# MSU_and_periphery.net
KiCad netlist of a schematic drawn in Altium Designer
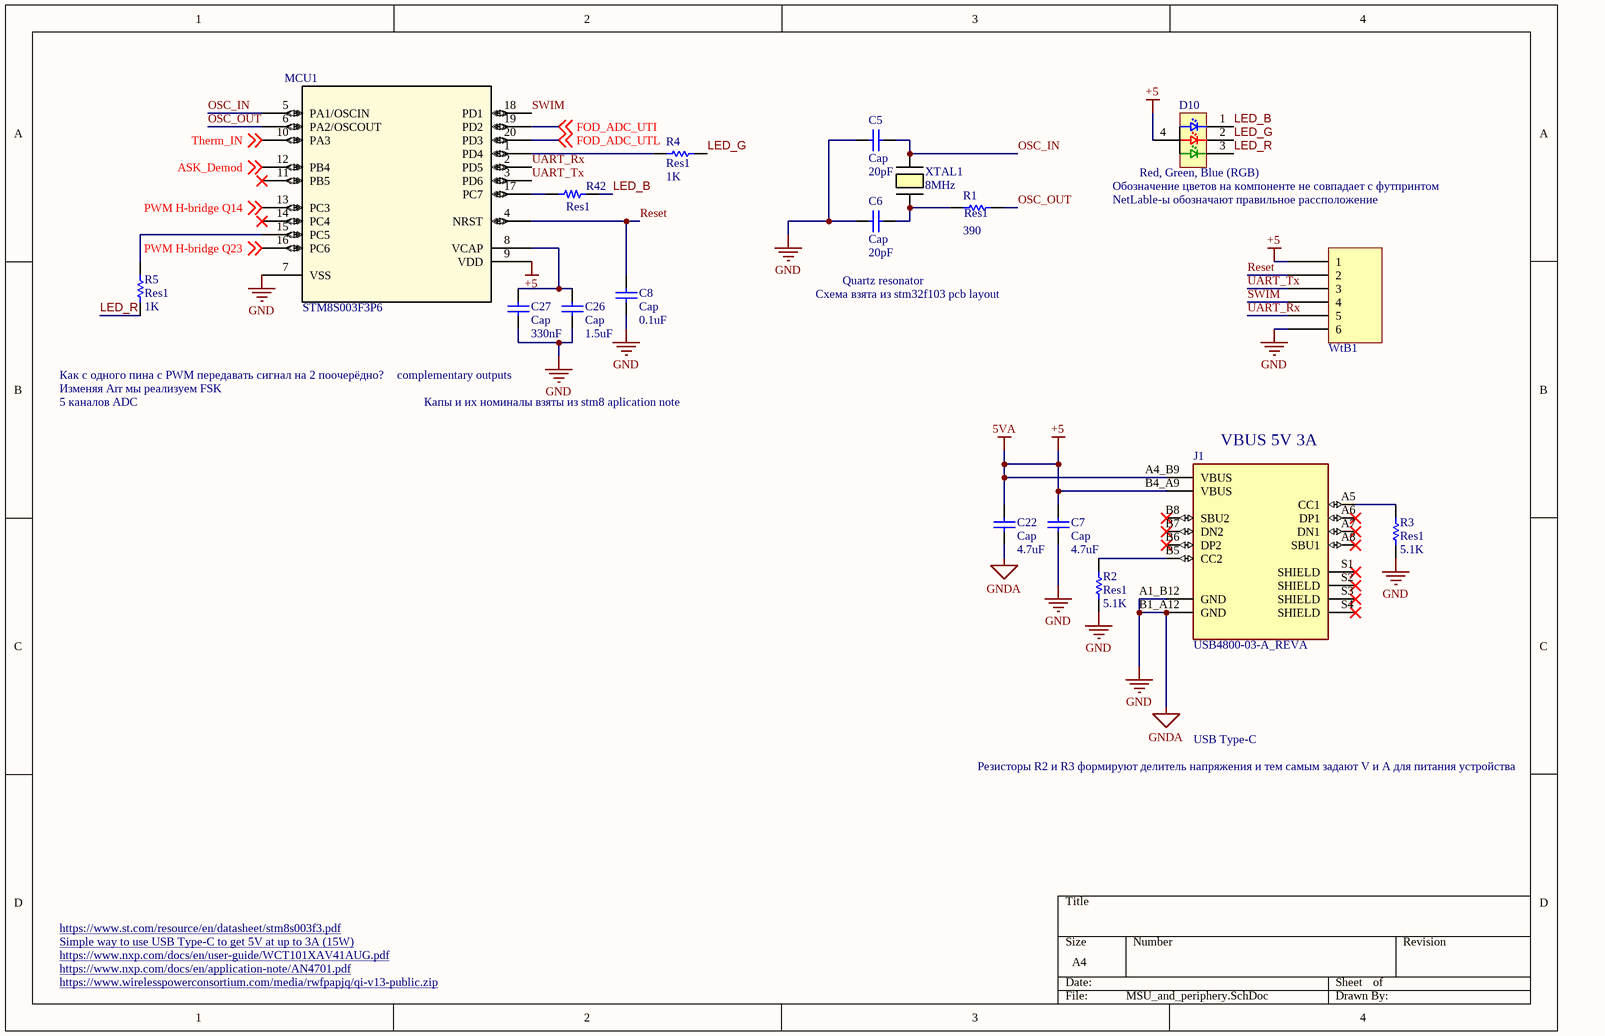
[diagram p0: MSU_and_periphery.SchDoc]

(export (version "E")
  (design (tool "Eeschema 10.0.6"))
  (components
    (comp (ref "C5")
      (value "Cap")
      (footprint "CAP 0402_1005")
      (description "Capacitor")
      (fields (field (name "ALTIUM_VALUE") "20pF") (field (name "PUBLISHER") "Altium Limited"))
      (libsource (lib "Miscellaneous Devices") (part "Cap"))
    )
    (comp (ref "C6")
      (value "Cap")
      (footprint "CAP 0402_1005")
      (description "Capacitor")
      (fields (field (name "ALTIUM_VALUE") "20pF") (field (name "PUBLISHER") "Altium Limited"))
      (libsource (lib "Miscellaneous Devices") (part "Cap"))
    )
    (comp (ref "C7")
      (value "Cap")
      (footprint "CAP 0402_1005")
      (description "Capacitor")
      (fields (field (name "ALTIUM_VALUE") "4.7uF") (field (name "PUBLISHER") "Altium Limited"))
      (libsource (lib "Miscellaneous Devices") (part "Cap"))
    )
    (comp (ref "C8")
      (value "Cap")
      (footprint "CAP 0402_1005")
      (description "Capacitor")
      (fields (field (name "ALTIUM_VALUE") "0.1uF") (field (name "PUBLISHER") "Altium Limited"))
      (libsource (lib "Miscellaneous Devices") (part "Cap"))
    )
    (comp (ref "C22")
      (value "Cap")
      (footprint "CAP 0402_1005")
      (description "Capacitor")
      (fields (field (name "ALTIUM_VALUE") "4.7uF") (field (name "PUBLISHER") "Altium Limited"))
      (libsource (lib "Miscellaneous Devices") (part "Cap"))
    )
    (comp (ref "C26")
      (value "Cap")
      (footprint "CAP 0603_1608")
      (description "Capacitor")
      (fields (field (name "ALTIUM_VALUE") "1.5uF") (field (name "PUBLISHER") "Altium Limited"))
      (libsource (lib "Miscellaneous Devices") (part "Cap"))
    )
    (comp (ref "C27")
      (value "Cap")
      (footprint "CAP 0603_1608")
      (description "Capacitor")
      (fields (field (name "ALTIUM_VALUE") "330nF") (field (name "PUBLISHER") "Altium Limited"))
      (libsource (lib "Miscellaneous Devices") (part "Cap"))
    )
    (comp (ref "D10")
      (value "Red, Green, Blue (RGB)")
      (footprint "Citizen CL-505S-X-SD-T")
      (description "LED TRI TOP FIRING 1.0 X 1.0")
      (fields (field (name "PART NUMBER") "CL-505S-X-SD-T") (field (name "MANUFACTURER") "Citizen"))
      (libsource (lib "LED - Indication") (part "CL-505S-X-SD-T"))
    )
    (comp (ref "J1")
      (value "USB4800-03-A_REVA")
      (footprint "GCT_USB4800-03-A_REVA")
      (fields (field (name "MP") "USB4800-03-A") (field (name "MF") "Global Connector Technology"))
      (libsource (lib "USB4800-03-A_REVA") (part "USB4800-03-A_REVA"))
    )
    (comp (ref "MCU1")
      (value "STM8S003F3P6")
      (footprint "TSSOP20")
      (description "No Description Available")
      (libsource (lib "STM8S003F3P6") (part "STM8S003F3P6"))
    )
    (comp (ref "R1")
      (value "Res1")
      (footprint "RES 0603_1608")
      (description "Resistor")
      (fields (field (name "ALTIUM_VALUE") "390") (field (name "PUBLISHER") "Altium Limited"))
      (libsource (lib "Miscellaneous Devices") (part "Res1"))
    )
    (comp (ref "R2")
      (value "Res1")
      (footprint "RES 0402_1005")
      (description "Resistor")
      (fields (field (name "ALTIUM_VALUE") "5.1K") (field (name "PUBLISHER") "Altium Limited"))
      (libsource (lib "Miscellaneous Devices") (part "Res1"))
    )
    (comp (ref "R3")
      (value "Res1")
      (footprint "RES 0402_1005")
      (description "Resistor")
      (fields (field (name "ALTIUM_VALUE") "5.1K") (field (name "PUBLISHER") "Altium Limited"))
      (libsource (lib "Miscellaneous Devices") (part "Res1"))
    )
    (comp (ref "R4")
      (value "Res1")
      (footprint "RES 0402_1005")
      (description "Resistor")
      (fields (field (name "ALTIUM_VALUE") "1K") (field (name "PUBLISHER") "Altium Limited"))
      (libsource (lib "Miscellaneous Devices") (part "Res1"))
    )
    (comp (ref "R5")
      (value "Res1")
      (footprint "RES 0402_1005")
      (description "Resistor")
      (fields (field (name "ALTIUM_VALUE") "1K") (field (name "PUBLISHER") "Altium Limited"))
      (libsource (lib "Miscellaneous Devices") (part "Res1"))
    )
    (comp (ref "R42")
      (value "Res1")
      (footprint "RES 0402_1005")
      (description "0402 JUMPER ON TAPE AND REEL")
      (fields (field (name "PART NUMBER") "5112") (field (name "MANUFACTURER") "Keystone Electronics"))
      (libsource (lib "Resistors - Surface Mount - 0402") (part "5112"))
    )
    (comp (ref "WtB1")
      (value "~")
      (footprint "6W_connector")
      (description "Wire to board connector 6pin")
      (libsource (lib "WtB_6_connector") (part "WtB_6_connector"))
    )
    (comp (ref "XTAL1")
      (value "8MHz")
      (footprint "NDK NX5032GA")
      (libsource (lib "ECS-80-18-5PX-TR") (part "ECS-80-18-5PX-TR"))
    )
  )
  (nets
    (net (code "1") (name "+5") (class "Default")
      (node (ref "C22") (pin "1") (pinfunction "1_1") (pintype "passive"))
      (node (ref "C7") (pin "1") (pinfunction "1_1") (pintype "passive"))
      (node (ref "D10") (pin "4") (pinfunction "A3_4") (pintype "passive"))
      (node (ref "J1") (pin "A4_B9") (pinfunction "VBUS_A4_B9") (pintype "power_in"))
      (node (ref "J1") (pin "B4_A9") (pinfunction "VBUS_B4_A9") (pintype "power_in"))
      (node (ref "MCU1") (pin "9") (pinfunction "VDD_9") (pintype "power_in"))
      (node (ref "WtB1") (pin "1") (pinfunction "1_1") (pintype "passive"))
    )
    (net (code "2") (name "/LED_B") (class "Default")
      (node (ref "D10") (pin "1") (pinfunction "C1_1") (pintype "passive"))
      (node (ref "R42") (pin "2") (pinfunction "2_2") (pintype "passive"))
    )
    (net (code "3") (name "/LED_G") (class "Default")
      (node (ref "D10") (pin "2") (pinfunction "C2_2") (pintype "passive"))
      (node (ref "R4") (pin "1") (pinfunction "1_1") (pintype "passive"))
    )
    (net (code "4") (name "/LED_R") (class "Default")
      (node (ref "D10") (pin "3") (pinfunction "C3_3") (pintype "passive"))
      (node (ref "R5") (pin "1") (pinfunction "1_1") (pintype "passive"))
    )
    (net (code "5") (name "/OSC_IN") (class "Default")
      (node (ref "C5") (pin "1") (pinfunction "1_1") (pintype "passive"))
      (node (ref "MCU1") (pin "5") (pinfunction "PA1/OSCIN_5") (pintype "bidirectional"))
      (node (ref "XTAL1") (pin "1") (pinfunction "4_1") (pintype "passive"))
    )
    (net (code "6") (name "/OSC_OUT") (class "Default")
      (node (ref "MCU1") (pin "6") (pinfunction "PA2/OSCOUT_6") (pintype "bidirectional"))
      (node (ref "R1") (pin "2") (pinfunction "2_2") (pintype "passive"))
    )
    (net (code "7") (name "/Reset") (class "Default")
      (node (ref "C8") (pin "2") (pinfunction "2_2") (pintype "passive"))
      (node (ref "MCU1") (pin "4") (pinfunction "NRST_4") (pintype "bidirectional"))
      (node (ref "WtB1") (pin "2") (pinfunction "2_2") (pintype "passive"))
    )
    (net (code "8") (name "/SWIM") (class "Default")
      (node (ref "MCU1") (pin "18") (pinfunction "PD1_18") (pintype "bidirectional"))
      (node (ref "WtB1") (pin "4") (pinfunction "4_4") (pintype "passive"))
    )
    (net (code "9") (name "/UART_Rx") (class "Default")
      (node (ref "MCU1") (pin "2") (pinfunction "PD5_2") (pintype "bidirectional"))
      (node (ref "WtB1") (pin "5") (pinfunction "5_5") (pintype "passive"))
    )
    (net (code "10") (name "/UART_Tx") (class "Default")
      (node (ref "MCU1") (pin "3") (pinfunction "PD6_3") (pintype "bidirectional"))
      (node (ref "WtB1") (pin "3") (pinfunction "3_3") (pintype "passive"))
    )
    (net (code "11") (name "ASK_Demod") (class "Default")
      (node (ref "MCU1") (pin "12") (pinfunction "PB4_12") (pintype "bidirectional"))
    )
    (net (code "12") (name "FOD_ADC_UTI") (class "Default")
      (node (ref "MCU1") (pin "19") (pinfunction "PD2_19") (pintype "bidirectional"))
    )
    (net (code "13") (name "FOD_ADC_UTL") (class "Default")
      (node (ref "MCU1") (pin "20") (pinfunction "PD3_20") (pintype "bidirectional"))
    )
    (net (code "14") (name "GND") (class "Default")
      (node (ref "C22") (pin "2") (pinfunction "2_2") (pintype "passive"))
      (node (ref "C26") (pin "2") (pinfunction "2_2") (pintype "passive"))
      (node (ref "C27") (pin "1") (pinfunction "1_1") (pintype "passive"))
      (node (ref "C5") (pin "2") (pinfunction "2_2") (pintype "passive"))
      (node (ref "C6") (pin "2") (pinfunction "2_2") (pintype "passive"))
      (node (ref "C7") (pin "2") (pinfunction "2_2") (pintype "passive"))
      (node (ref "C8") (pin "1") (pinfunction "1_1") (pintype "passive"))
      (node (ref "J1") (pin "A1_B12") (pinfunction "GND_A1_B12") (pintype "power_in"))
      (node (ref "J1") (pin "B1_A12") (pinfunction "GND_B1_A12") (pintype "power_in"))
      (node (ref "MCU1") (pin "7") (pinfunction "VSS_7") (pintype "power_in"))
      (node (ref "R2") (pin "2") (pinfunction "2_2") (pintype "passive"))
      (node (ref "R3") (pin "2") (pinfunction "2_2") (pintype "passive"))
      (node (ref "WtB1") (pin "6") (pinfunction "6_6") (pintype "passive"))
    )
    (net (code "15") (name "Net-(C6-Pad1)") (class "Default")
      (node (ref "C6") (pin "1") (pinfunction "1_1") (pintype "passive"))
      (node (ref "R1") (pin "1") (pinfunction "1_1") (pintype "passive"))
      (node (ref "XTAL1") (pin "2") (pinfunction "2_2") (pintype "passive"))
    )
    (net (code "16") (name "Net-(J1-CC1)") (class "Default")
      (node (ref "J1") (pin "A5") (pinfunction "CC1_A5") (pintype "bidirectional"))
      (node (ref "R3") (pin "1") (pinfunction "1_1") (pintype "passive"))
    )
    (net (code "17") (name "Net-(J1-CC2)") (class "Default")
      (node (ref "J1") (pin "B5") (pinfunction "CC2_B5") (pintype "bidirectional"))
      (node (ref "R2") (pin "1") (pinfunction "1_1") (pintype "passive"))
    )
    (net (code "18") (name "Net-(MCU1-PC5)") (class "Default")
      (node (ref "MCU1") (pin "15") (pinfunction "PC5_15") (pintype "bidirectional"))
      (node (ref "R5") (pin "2") (pinfunction "2_2") (pintype "passive"))
    )
    (net (code "19") (name "Net-(MCU1-PC7)") (class "Default")
      (node (ref "MCU1") (pin "17") (pinfunction "PC7_17") (pintype "bidirectional"))
      (node (ref "R42") (pin "1") (pinfunction "1_1") (pintype "passive"))
    )
    (net (code "20") (name "Net-(MCU1-PD4)") (class "Default")
      (node (ref "MCU1") (pin "1") (pinfunction "PD4_1") (pintype "bidirectional"))
      (node (ref "R4") (pin "2") (pinfunction "2_2") (pintype "passive"))
    )
    (net (code "21") (name "Net-(MCU1-VCAP)") (class "Default")
      (node (ref "C26") (pin "1") (pinfunction "1_1") (pintype "passive"))
      (node (ref "C27") (pin "2") (pinfunction "2_2") (pintype "passive"))
      (node (ref "MCU1") (pin "8") (pinfunction "VCAP_8") (pintype "power_in"))
    )
    (net (code "22") (name "PWM H-bridge Q14") (class "Default")
      (node (ref "MCU1") (pin "13") (pinfunction "PC3_13") (pintype "bidirectional"))
    )
    (net (code "23") (name "PWM H-bridge Q23") (class "Default")
      (node (ref "MCU1") (pin "16") (pinfunction "PC6_16") (pintype "bidirectional"))
    )
    (net (code "24") (name "Therm_IN") (class "Default")
      (node (ref "MCU1") (pin "10") (pinfunction "PA3_10") (pintype "bidirectional"))
    )
    (net (code "25") (name "unconnected-(J1-DN1-PadA7)") (class "Default")
      (node (ref "J1") (pin "A7") (pinfunction "DN1_A7") (pintype "bidirectional+no_connect"))
    )
    (net (code "26") (name "unconnected-(J1-DN2-PadB7)") (class "Default")
      (node (ref "J1") (pin "B7") (pinfunction "DN2_B7") (pintype "bidirectional+no_connect"))
    )
    (net (code "27") (name "unconnected-(J1-DP1-PadA6)") (class "Default")
      (node (ref "J1") (pin "A6") (pinfunction "DP1_A6") (pintype "bidirectional+no_connect"))
    )
    (net (code "28") (name "unconnected-(J1-DP2-PadB6)") (class "Default")
      (node (ref "J1") (pin "B6") (pinfunction "DP2_B6") (pintype "bidirectional+no_connect"))
    )
    (net (code "29") (name "unconnected-(J1-SBU1-PadA8)") (class "Default")
      (node (ref "J1") (pin "A8") (pinfunction "SBU1_A8") (pintype "bidirectional+no_connect"))
    )
    (net (code "30") (name "unconnected-(J1-SBU2-PadB8)") (class "Default")
      (node (ref "J1") (pin "B8") (pinfunction "SBU2_B8") (pintype "bidirectional+no_connect"))
    )
    (net (code "31") (name "unconnected-(J1-SHIELD-PadS1)") (class "Default")
      (node (ref "J1") (pin "S1") (pinfunction "SHIELD_S1") (pintype "passive+no_connect"))
    )
    (net (code "32") (name "unconnected-(J1-SHIELD-PadS2)") (class "Default")
      (node (ref "J1") (pin "S2") (pinfunction "SHIELD_S2") (pintype "passive+no_connect"))
    )
    (net (code "33") (name "unconnected-(J1-SHIELD-PadS3)") (class "Default")
      (node (ref "J1") (pin "S3") (pinfunction "SHIELD_S3") (pintype "passive+no_connect"))
    )
    (net (code "34") (name "unconnected-(J1-SHIELD-PadS4)") (class "Default")
      (node (ref "J1") (pin "S4") (pinfunction "SHIELD_S4") (pintype "passive+no_connect"))
    )
    (net (code "35") (name "unconnected-(MCU1-PB5-Pad11)") (class "Default")
      (node (ref "MCU1") (pin "11") (pinfunction "PB5_11") (pintype "bidirectional+no_connect"))
    )
    (net (code "36") (name "unconnected-(MCU1-PC4-Pad14)") (class "Default")
      (node (ref "MCU1") (pin "14") (pinfunction "PC4_14") (pintype "bidirectional+no_connect"))
    )
  )
)
